# FPGA_-_Decoupling.net
KiCad netlist of a schematic drawn in Altium Designer
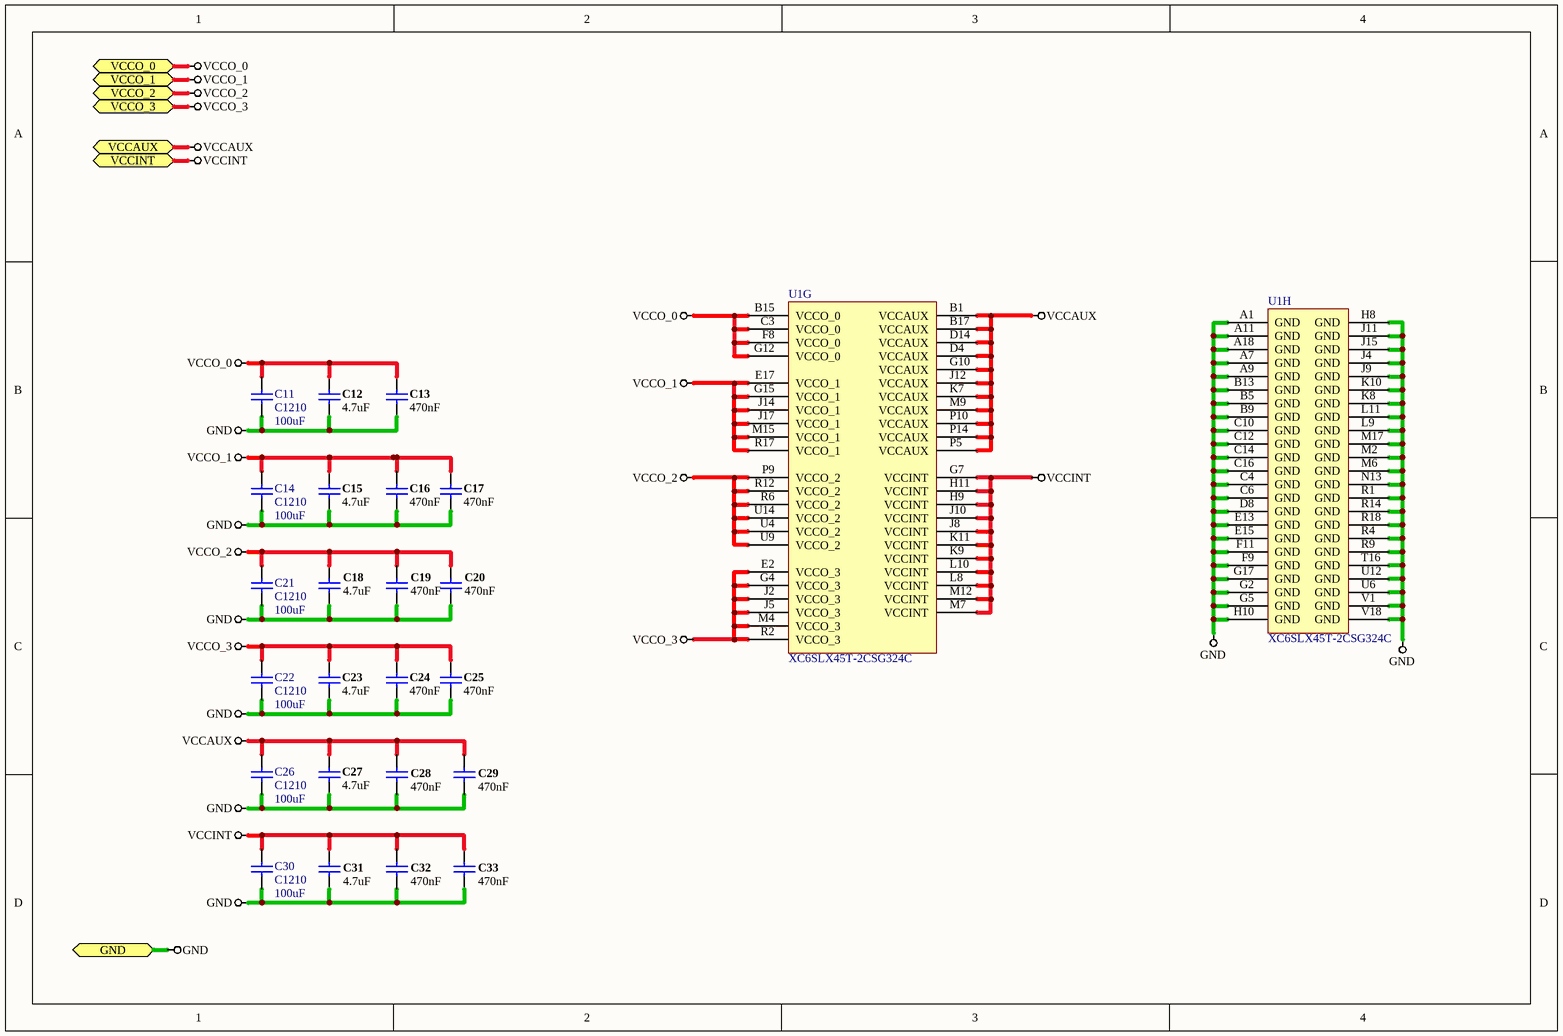
[diagram p0: FPGA - Decoupling.SchDoc]

(export (version "E")
  (design (tool "Eeschema 10.0.6"))
  (components
    (comp (ref "C11")
      (value "C1210")
      (footprint "C-1210")
      (description "GRM32ER60J107ME20L")
      (fields (field (name "ALTIUM_VALUE") "100uF"))
      (libsource (lib "FPGA-pcie") (part "C1210"))
    )
    (comp (ref "C12")
      (value "4.7uF")
      (footprint "CAPC0603(1608)55_L")
      (fields
        (field (name "TOLERANCE") "±10%")
        (field (name "MANUFACTURER PART NUMBER") "CC0603KRX5R6BB475")
        (field (name "Comment") "CAP 4.7uF 10V 0603(1608)")
      )
      (libsource (lib "Component_Database") (part "CAP_NP"))
    )
    (comp (ref "C13")
      (value "470nF")
      (footprint "CAPC0402(1005)60_L")
      (fields
        (field (name "TOLERANCE") "±10%")
        (field (name "MANUFACTURER PART NUMBER") "LMK105BJ474KV-F")
        (field (name "Comment") "CAP 470nF 10V 0402(1005)")
      )
      (libsource (lib "Component_Database") (part "CAP_NP"))
    )
    (comp (ref "C14")
      (value "C1210")
      (footprint "C-1210")
      (description "GRM32ER60J107ME20L")
      (fields (field (name "ALTIUM_VALUE") "100uF"))
      (libsource (lib "FPGA-pcie") (part "C1210"))
    )
    (comp (ref "C15")
      (value "4.7uF")
      (footprint "CAPC0603(1608)55_L")
      (fields
        (field (name "TOLERANCE") "±10%")
        (field (name "MANUFACTURER PART NUMBER") "CC0603KRX5R6BB475")
        (field (name "Comment") "CAP 4.7uF 10V 0603(1608)")
      )
      (libsource (lib "Component_Database") (part "CAP_NP"))
    )
    (comp (ref "C16")
      (value "470nF")
      (footprint "CAPC0402(1005)60_L")
      (fields
        (field (name "TOLERANCE") "±10%")
        (field (name "MANUFACTURER PART NUMBER") "LMK105BJ474KV-F")
        (field (name "Comment") "CAP 470nF 10V 0402(1005)")
      )
      (libsource (lib "Component_Database") (part "CAP_NP"))
    )
    (comp (ref "C17")
      (value "470nF")
      (footprint "CAPC0402(1005)60_L")
      (fields
        (field (name "TOLERANCE") "±10%")
        (field (name "MANUFACTURER PART NUMBER") "LMK105BJ474KV-F")
        (field (name "Comment") "CAP 470nF 10V 0402(1005)")
      )
      (libsource (lib "Component_Database") (part "CAP_NP"))
    )
    (comp (ref "C18")
      (value "4.7uF")
      (footprint "CAPC0603(1608)55_L")
      (fields
        (field (name "TOLERANCE") "±10%")
        (field (name "MANUFACTURER PART NUMBER") "CC0603KRX5R6BB475")
        (field (name "Comment") "CAP 4.7uF 10V 0603(1608)")
      )
      (libsource (lib "Component_Database") (part "CAP_NP"))
    )
    (comp (ref "C19")
      (value "470nF")
      (footprint "CAPC0402(1005)60_L")
      (fields
        (field (name "TOLERANCE") "±10%")
        (field (name "MANUFACTURER PART NUMBER") "LMK105BJ474KV-F")
        (field (name "Comment") "CAP 470nF 10V 0402(1005)")
      )
      (libsource (lib "Component_Database") (part "CAP_NP"))
    )
    (comp (ref "C20")
      (value "470nF")
      (footprint "CAPC0402(1005)60_L")
      (fields
        (field (name "TOLERANCE") "±10%")
        (field (name "MANUFACTURER PART NUMBER") "LMK105BJ474KV-F")
        (field (name "Comment") "CAP 470nF 10V 0402(1005)")
      )
      (libsource (lib "Component_Database") (part "CAP_NP"))
    )
    (comp (ref "C21")
      (value "C1210")
      (footprint "C-1210")
      (description "GRM32ER60J107ME20L")
      (fields (field (name "ALTIUM_VALUE") "100uF"))
      (libsource (lib "FPGA-pcie") (part "C1210"))
    )
    (comp (ref "C22")
      (value "C1210")
      (footprint "C-1210")
      (description "GRM32ER60J107ME20L")
      (fields (field (name "ALTIUM_VALUE") "100uF"))
      (libsource (lib "FPGA-pcie") (part "C1210"))
    )
    (comp (ref "C23")
      (value "4.7uF")
      (footprint "CAPC0603(1608)55_L")
      (fields
        (field (name "TOLERANCE") "±10%")
        (field (name "MANUFACTURER PART NUMBER") "CC0603KRX5R6BB475")
        (field (name "Comment") "CAP 4.7uF 10V 0603(1608)")
      )
      (libsource (lib "Component_Database") (part "CAP_NP"))
    )
    (comp (ref "C24")
      (value "470nF")
      (footprint "CAPC0402(1005)60_L")
      (fields
        (field (name "TOLERANCE") "±10%")
        (field (name "MANUFACTURER PART NUMBER") "LMK105BJ474KV-F")
        (field (name "Comment") "CAP 470nF 10V 0402(1005)")
      )
      (libsource (lib "Component_Database") (part "CAP_NP"))
    )
    (comp (ref "C25")
      (value "470nF")
      (footprint "CAPC0402(1005)60_L")
      (fields
        (field (name "TOLERANCE") "±10%")
        (field (name "MANUFACTURER PART NUMBER") "LMK105BJ474KV-F")
        (field (name "Comment") "CAP 470nF 10V 0402(1005)")
      )
      (libsource (lib "Component_Database") (part "CAP_NP"))
    )
    (comp (ref "C26")
      (value "C1210")
      (footprint "C-1210")
      (description "GRM32ER60J107ME20L")
      (fields (field (name "ALTIUM_VALUE") "100uF"))
      (libsource (lib "FPGA-pcie") (part "C1210"))
    )
    (comp (ref "C27")
      (value "4.7uF")
      (footprint "CAPC0603(1608)55_L")
      (fields
        (field (name "TOLERANCE") "±10%")
        (field (name "MANUFACTURER PART NUMBER") "CC0603KRX5R6BB475")
        (field (name "Comment") "CAP 4.7uF 10V 0603(1608)")
      )
      (libsource (lib "Component_Database") (part "CAP_NP"))
    )
    (comp (ref "C28")
      (value "470nF")
      (footprint "CAPC0402(1005)60_L")
      (fields
        (field (name "TOLERANCE") "±10%")
        (field (name "MANUFACTURER PART NUMBER") "LMK105BJ474KV-F")
        (field (name "Comment") "CAP 470nF 10V 0402(1005)")
      )
      (libsource (lib "Component_Database") (part "CAP_NP"))
    )
    (comp (ref "C29")
      (value "470nF")
      (footprint "CAPC0402(1005)60_L")
      (fields
        (field (name "TOLERANCE") "±10%")
        (field (name "MANUFACTURER PART NUMBER") "LMK105BJ474KV-F")
        (field (name "Comment") "CAP 470nF 10V 0402(1005)")
      )
      (libsource (lib "Component_Database") (part "CAP_NP"))
    )
    (comp (ref "C30")
      (value "C1210")
      (footprint "C-1210")
      (description "GRM32ER60J107ME20L")
      (fields (field (name "ALTIUM_VALUE") "100uF"))
      (libsource (lib "FPGA-pcie") (part "C1210"))
    )
    (comp (ref "C31")
      (value "4.7uF")
      (footprint "CAPC0603(1608)55_L")
      (fields
        (field (name "TOLERANCE") "±10%")
        (field (name "MANUFACTURER PART NUMBER") "CC0603KRX5R6BB475")
        (field (name "Comment") "CAP 4.7uF 10V 0603(1608)")
      )
      (libsource (lib "Component_Database") (part "CAP_NP"))
    )
    (comp (ref "C32")
      (value "470nF")
      (footprint "CAPC0402(1005)60_L")
      (fields
        (field (name "TOLERANCE") "±10%")
        (field (name "MANUFACTURER PART NUMBER") "LMK105BJ474KV-F")
        (field (name "Comment") "CAP 470nF 10V 0402(1005)")
      )
      (libsource (lib "Component_Database") (part "CAP_NP"))
    )
    (comp (ref "C33")
      (value "470nF")
      (footprint "CAPC0402(1005)60_L")
      (fields
        (field (name "TOLERANCE") "±10%")
        (field (name "MANUFACTURER PART NUMBER") "LMK105BJ474KV-F")
        (field (name "Comment") "CAP 470nF 10V 0402(1005)")
      )
      (libsource (lib "Component_Database") (part "CAP_NP"))
    )
    (comp (ref "U1")
      (value "XC6SLX45T-2CSG324C")
      (footprint "CSG324")
      (fields (field (name "PUBLISHER") "Altium Limited"))
      (libsource (lib "Xilinx Spartan-6") (part "XC6SLX45T-2CSG324C"))
    )
  )
  (nets
    (net (code "1") (name "GND") (class "Default")
      (node (ref "C11") (pin "1") (pinfunction "1_1") (pintype "passive"))
      (node (ref "C12") (pin "1") (pinfunction "1_1") (pintype "passive"))
      (node (ref "C13") (pin "1") (pinfunction "1_1") (pintype "passive"))
      (node (ref "C14") (pin "1") (pinfunction "1_1") (pintype "passive"))
      (node (ref "C15") (pin "1") (pinfunction "1_1") (pintype "passive"))
      (node (ref "C16") (pin "1") (pinfunction "1_1") (pintype "passive"))
      (node (ref "C17") (pin "1") (pinfunction "1_1") (pintype "passive"))
      (node (ref "C18") (pin "1") (pinfunction "1_1") (pintype "passive"))
      (node (ref "C19") (pin "1") (pinfunction "1_1") (pintype "passive"))
      (node (ref "C20") (pin "1") (pinfunction "1_1") (pintype "passive"))
      (node (ref "C21") (pin "1") (pinfunction "1_1") (pintype "passive"))
      (node (ref "C22") (pin "1") (pinfunction "1_1") (pintype "passive"))
      (node (ref "C23") (pin "1") (pinfunction "1_1") (pintype "passive"))
      (node (ref "C24") (pin "1") (pinfunction "1_1") (pintype "passive"))
      (node (ref "C25") (pin "1") (pinfunction "1_1") (pintype "passive"))
      (node (ref "C26") (pin "1") (pinfunction "1_1") (pintype "passive"))
      (node (ref "C27") (pin "2") (pinfunction "2_2") (pintype "passive"))
      (node (ref "C28") (pin "2") (pinfunction "2_2") (pintype "passive"))
      (node (ref "C29") (pin "2") (pinfunction "2_2") (pintype "passive"))
      (node (ref "C30") (pin "1") (pinfunction "1_1") (pintype "passive"))
      (node (ref "C31") (pin "2") (pinfunction "2_2") (pintype "passive"))
      (node (ref "C32") (pin "2") (pinfunction "2_2") (pintype "passive"))
      (node (ref "C33") (pin "2") (pinfunction "2_2") (pintype "passive"))
      (node (ref "U1") (pin "A1") (pinfunction "GND_A1") (pintype "power_in"))
      (node (ref "U1") (pin "A11") (pinfunction "GND_A11") (pintype "power_in"))
      (node (ref "U1") (pin "A18") (pinfunction "GND_A18") (pintype "power_in"))
      (node (ref "U1") (pin "A7") (pinfunction "GND_A7") (pintype "power_in"))
      (node (ref "U1") (pin "A9") (pinfunction "GND_A9") (pintype "power_in"))
      (node (ref "U1") (pin "B13") (pinfunction "GND_B13") (pintype "power_in"))
      (node (ref "U1") (pin "B5") (pinfunction "GND_B5") (pintype "power_in"))
      (node (ref "U1") (pin "B9") (pinfunction "GND_B9") (pintype "power_in"))
      (node (ref "U1") (pin "C10") (pinfunction "GND_C10") (pintype "power_in"))
      (node (ref "U1") (pin "C12") (pinfunction "GND_C12") (pintype "power_in"))
      (node (ref "U1") (pin "C14") (pinfunction "GND_C14") (pintype "power_in"))
      (node (ref "U1") (pin "C16") (pinfunction "GND_C16") (pintype "power_in"))
      (node (ref "U1") (pin "C4") (pinfunction "GND_C4") (pintype "power_in"))
      (node (ref "U1") (pin "C6") (pinfunction "GND_C6") (pintype "power_in"))
      (node (ref "U1") (pin "D8") (pinfunction "GND_D8") (pintype "power_in"))
      (node (ref "U1") (pin "E13") (pinfunction "GND_E13") (pintype "power_in"))
      (node (ref "U1") (pin "E15") (pinfunction "GND_E15") (pintype "power_in"))
      (node (ref "U1") (pin "F11") (pinfunction "GND_F11") (pintype "power_in"))
      (node (ref "U1") (pin "F9") (pinfunction "GND_F9") (pintype "power_in"))
      (node (ref "U1") (pin "G17") (pinfunction "GND_G17") (pintype "power_in"))
      (node (ref "U1") (pin "G2") (pinfunction "GND_G2") (pintype "power_in"))
      (node (ref "U1") (pin "G5") (pinfunction "GND_G5") (pintype "power_in"))
      (node (ref "U1") (pin "H10") (pinfunction "GND_H10") (pintype "power_in"))
      (node (ref "U1") (pin "H8") (pinfunction "GND_H8") (pintype "power_in"))
      (node (ref "U1") (pin "J11") (pinfunction "GND_J11") (pintype "power_in"))
      (node (ref "U1") (pin "J15") (pinfunction "GND_J15") (pintype "power_in"))
      (node (ref "U1") (pin "J4") (pinfunction "GND_J4") (pintype "power_in"))
      (node (ref "U1") (pin "J9") (pinfunction "GND_J9") (pintype "power_in"))
      (node (ref "U1") (pin "K10") (pinfunction "GND_K10") (pintype "power_in"))
      (node (ref "U1") (pin "K8") (pinfunction "GND_K8") (pintype "power_in"))
      (node (ref "U1") (pin "L11") (pinfunction "GND_L11") (pintype "power_in"))
      (node (ref "U1") (pin "L9") (pinfunction "GND_L9") (pintype "power_in"))
      (node (ref "U1") (pin "M17") (pinfunction "GND_M17") (pintype "power_in"))
      (node (ref "U1") (pin "M2") (pinfunction "GND_M2") (pintype "power_in"))
      (node (ref "U1") (pin "M6") (pinfunction "GND_M6") (pintype "power_in"))
      (node (ref "U1") (pin "N13") (pinfunction "GND_N13") (pintype "power_in"))
      (node (ref "U1") (pin "R1") (pinfunction "GND_R1") (pintype "power_in"))
      (node (ref "U1") (pin "R14") (pinfunction "GND_R14") (pintype "power_in"))
      (node (ref "U1") (pin "R18") (pinfunction "GND_R18") (pintype "power_in"))
      (node (ref "U1") (pin "R4") (pinfunction "GND_R4") (pintype "power_in"))
      (node (ref "U1") (pin "R9") (pinfunction "GND_R9") (pintype "power_in"))
      (node (ref "U1") (pin "T16") (pinfunction "GND_T16") (pintype "power_in"))
      (node (ref "U1") (pin "U12") (pinfunction "GND_U12") (pintype "power_in"))
      (node (ref "U1") (pin "U6") (pinfunction "GND_U6") (pintype "power_in"))
      (node (ref "U1") (pin "V1") (pinfunction "GND_V1") (pintype "power_in"))
      (node (ref "U1") (pin "V18") (pinfunction "GND_V18") (pintype "power_in"))
    )
    (net (code "2") (name "VCCAUX") (class "Default")
      (node (ref "C26") (pin "2") (pinfunction "2_2") (pintype "passive"))
      (node (ref "C27") (pin "1") (pinfunction "1_1") (pintype "passive"))
      (node (ref "C28") (pin "1") (pinfunction "1_1") (pintype "passive"))
      (node (ref "C29") (pin "1") (pinfunction "1_1") (pintype "passive"))
      (node (ref "U1") (pin "B1") (pinfunction "VCCAUX_B1") (pintype "power_in"))
      (node (ref "U1") (pin "B17") (pinfunction "VCCAUX_B17") (pintype "power_in"))
      (node (ref "U1") (pin "D14") (pinfunction "VCCAUX_D14") (pintype "power_in"))
      (node (ref "U1") (pin "D4") (pinfunction "VCCAUX_D4") (pintype "power_in"))
      (node (ref "U1") (pin "G10") (pinfunction "VCCAUX_G10") (pintype "power_in"))
      (node (ref "U1") (pin "J12") (pinfunction "VCCAUX_J12") (pintype "power_in"))
      (node (ref "U1") (pin "K7") (pinfunction "VCCAUX_K7") (pintype "power_in"))
      (node (ref "U1") (pin "M9") (pinfunction "VCCAUX_M9") (pintype "power_in"))
      (node (ref "U1") (pin "P10") (pinfunction "VCCAUX_P10") (pintype "power_in"))
      (node (ref "U1") (pin "P14") (pinfunction "VCCAUX_P14") (pintype "power_in"))
      (node (ref "U1") (pin "P5") (pinfunction "VCCAUX_P5") (pintype "power_in"))
    )
    (net (code "3") (name "VCCINT") (class "Default")
      (node (ref "C30") (pin "2") (pinfunction "2_2") (pintype "passive"))
      (node (ref "C31") (pin "1") (pinfunction "1_1") (pintype "passive"))
      (node (ref "C32") (pin "1") (pinfunction "1_1") (pintype "passive"))
      (node (ref "C33") (pin "1") (pinfunction "1_1") (pintype "passive"))
      (node (ref "U1") (pin "G7") (pinfunction "VCCINT_G7") (pintype "power_in"))
      (node (ref "U1") (pin "H11") (pinfunction "VCCINT_H11") (pintype "power_in"))
      (node (ref "U1") (pin "H9") (pinfunction "VCCINT_H9") (pintype "power_in"))
      (node (ref "U1") (pin "J10") (pinfunction "VCCINT_J10") (pintype "power_in"))
      (node (ref "U1") (pin "J8") (pinfunction "VCCINT_J8") (pintype "power_in"))
      (node (ref "U1") (pin "K11") (pinfunction "VCCINT_K11") (pintype "power_in"))
      (node (ref "U1") (pin "K9") (pinfunction "VCCINT_K9") (pintype "power_in"))
      (node (ref "U1") (pin "L10") (pinfunction "VCCINT_L10") (pintype "power_in"))
      (node (ref "U1") (pin "L8") (pinfunction "VCCINT_L8") (pintype "power_in"))
      (node (ref "U1") (pin "M12") (pinfunction "VCCINT_M12") (pintype "power_in"))
      (node (ref "U1") (pin "M7") (pinfunction "VCCINT_M7") (pintype "power_in"))
    )
    (net (code "4") (name "VCCO_0") (class "Default")
      (node (ref "C11") (pin "2") (pinfunction "2_2") (pintype "passive"))
      (node (ref "C12") (pin "2") (pinfunction "2_2") (pintype "passive"))
      (node (ref "C13") (pin "2") (pinfunction "2_2") (pintype "passive"))
      (node (ref "U1") (pin "B15") (pinfunction "VCCO_0_B15") (pintype "power_in"))
      (node (ref "U1") (pin "C3") (pinfunction "VCCO_0_C3") (pintype "power_in"))
      (node (ref "U1") (pin "F8") (pinfunction "VCCO_0_F8") (pintype "power_in"))
      (node (ref "U1") (pin "G12") (pinfunction "VCCO_0_G12") (pintype "power_in"))
    )
    (net (code "5") (name "VCCO_1") (class "Default")
      (node (ref "C14") (pin "2") (pinfunction "2_2") (pintype "passive"))
      (node (ref "C15") (pin "2") (pinfunction "2_2") (pintype "passive"))
      (node (ref "C16") (pin "2") (pinfunction "2_2") (pintype "passive"))
      (node (ref "C17") (pin "2") (pinfunction "2_2") (pintype "passive"))
      (node (ref "U1") (pin "E17") (pinfunction "VCCO_1_E17") (pintype "power_in"))
      (node (ref "U1") (pin "G15") (pinfunction "VCCO_1_G15") (pintype "power_in"))
      (node (ref "U1") (pin "J14") (pinfunction "VCCO_1_J14") (pintype "power_in"))
      (node (ref "U1") (pin "J17") (pinfunction "VCCO_1_J17") (pintype "power_in"))
      (node (ref "U1") (pin "M15") (pinfunction "VCCO_1_M15") (pintype "power_in"))
      (node (ref "U1") (pin "R17") (pinfunction "VCCO_1_R17") (pintype "power_in"))
    )
    (net (code "6") (name "VCCO_2") (class "Default")
      (node (ref "C18") (pin "2") (pinfunction "2_2") (pintype "passive"))
      (node (ref "C19") (pin "2") (pinfunction "2_2") (pintype "passive"))
      (node (ref "C20") (pin "2") (pinfunction "2_2") (pintype "passive"))
      (node (ref "C21") (pin "2") (pinfunction "2_2") (pintype "passive"))
      (node (ref "U1") (pin "P9") (pinfunction "VCCO_2_P9") (pintype "power_in"))
      (node (ref "U1") (pin "R12") (pinfunction "VCCO_2_R12") (pintype "power_in"))
      (node (ref "U1") (pin "R6") (pinfunction "VCCO_2_R6") (pintype "power_in"))
      (node (ref "U1") (pin "U14") (pinfunction "VCCO_2_U14") (pintype "power_in"))
      (node (ref "U1") (pin "U4") (pinfunction "VCCO_2_U4") (pintype "power_in"))
      (node (ref "U1") (pin "U9") (pinfunction "VCCO_2_U9") (pintype "power_in"))
    )
    (net (code "7") (name "VCCO_3") (class "Default")
      (node (ref "C22") (pin "2") (pinfunction "2_2") (pintype "passive"))
      (node (ref "C23") (pin "2") (pinfunction "2_2") (pintype "passive"))
      (node (ref "C24") (pin "2") (pinfunction "2_2") (pintype "passive"))
      (node (ref "C25") (pin "2") (pinfunction "2_2") (pintype "passive"))
      (node (ref "U1") (pin "E2") (pinfunction "VCCO_3_E2") (pintype "power_in"))
      (node (ref "U1") (pin "G4") (pinfunction "VCCO_3_G4") (pintype "power_in"))
      (node (ref "U1") (pin "J2") (pinfunction "VCCO_3_J2") (pintype "power_in"))
      (node (ref "U1") (pin "J5") (pinfunction "VCCO_3_J5") (pintype "power_in"))
      (node (ref "U1") (pin "M4") (pinfunction "VCCO_3_M4") (pintype "power_in"))
      (node (ref "U1") (pin "R2") (pinfunction "VCCO_3_R2") (pintype "power_in"))
    )
  )
)
